# Raspi-TPUART_v1_2.net
KiCad netlist of a schematic drawn in EAGLE
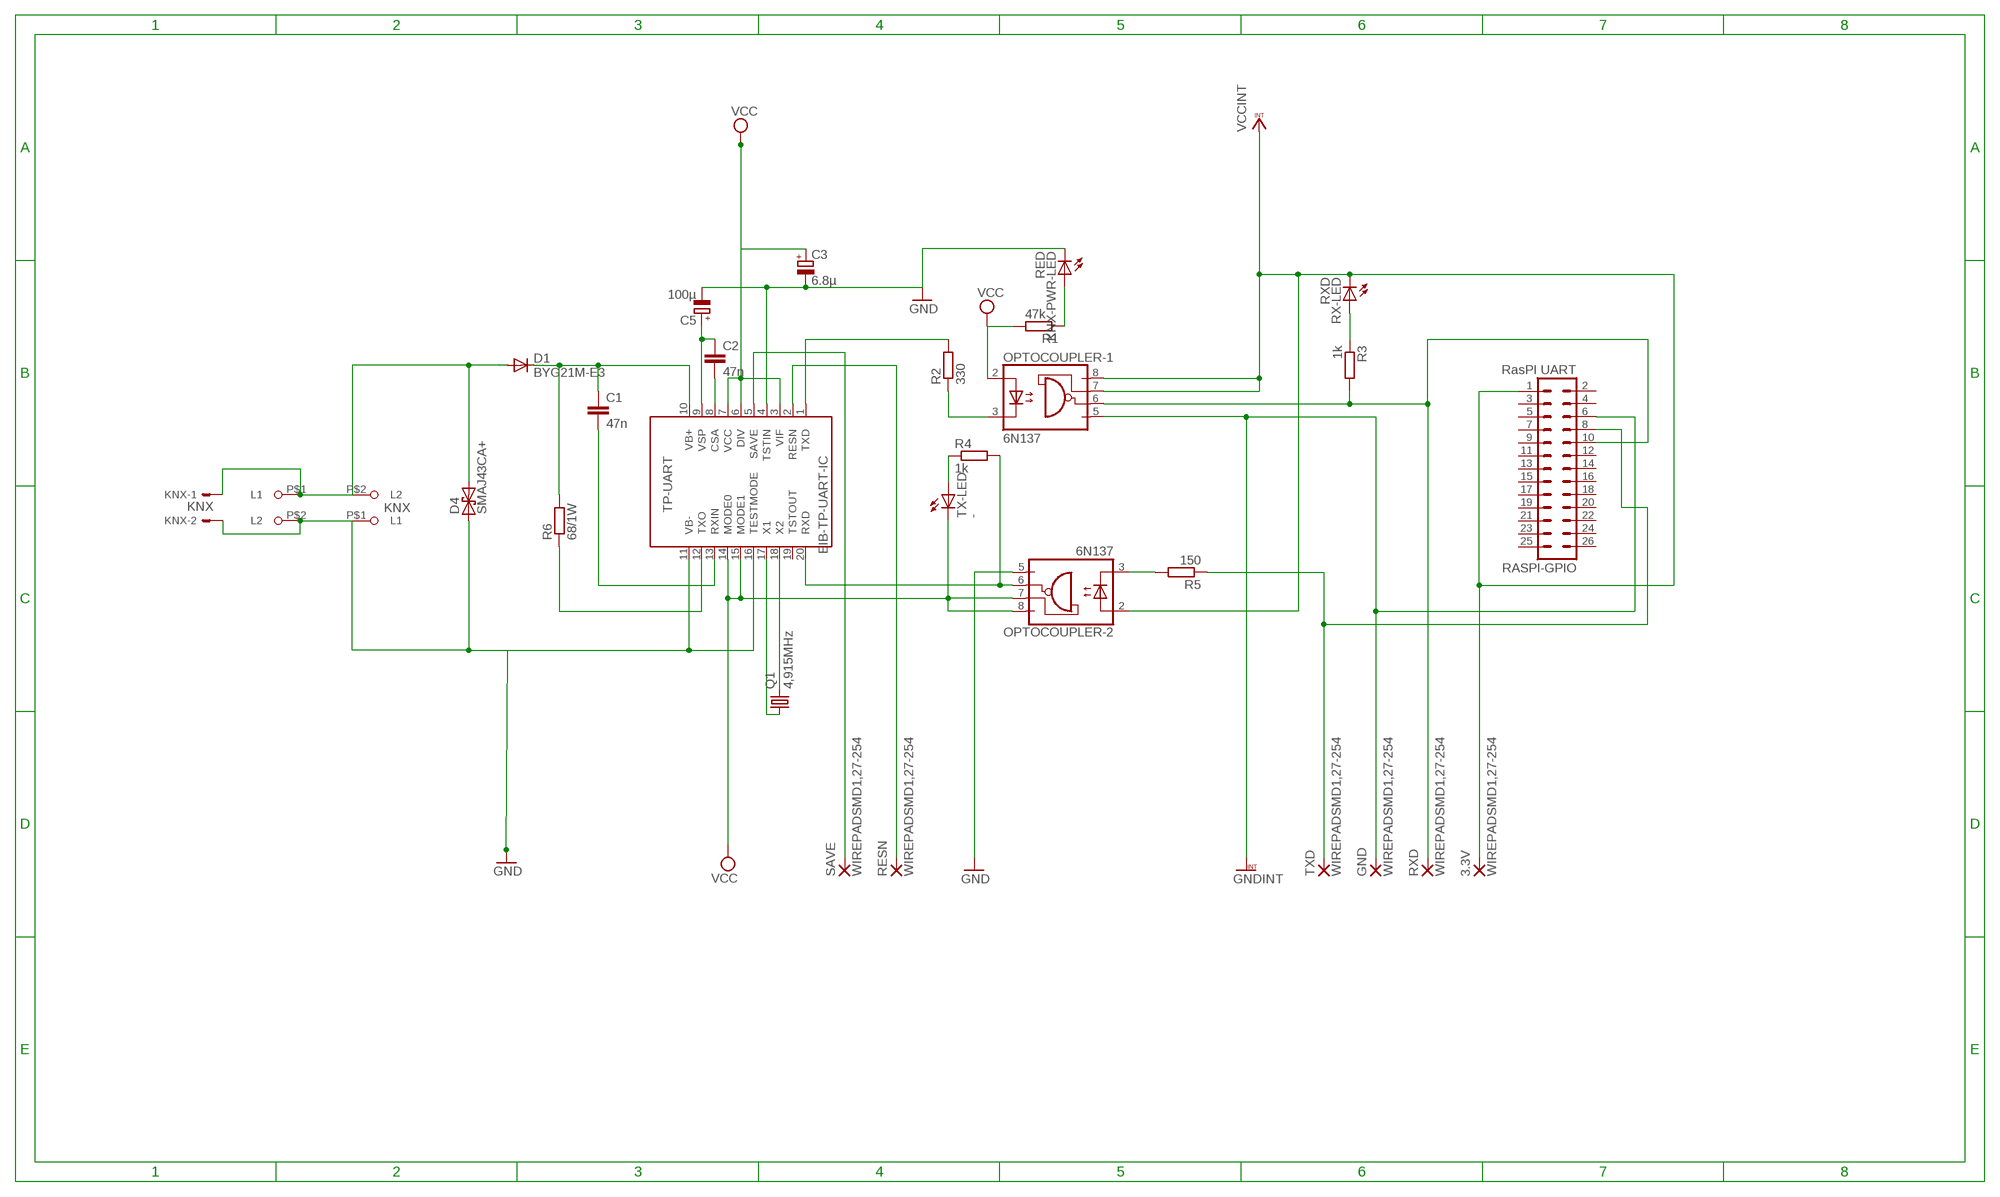
[diagram p0: schematic, sheet 1]

(export (version "E")
  (design (tool "Eeschema 10.0.6"))
  (components
    (comp (ref "3.3V")
      (value "WIREPADSMD1,27-254")
      (footprint "eagle-import:SMD1,27-2,54")
      (libsource (lib "eagle-import") (part "WIREPADSMD1,27-254"))
    )
    (comp (ref "C1")
      (value "47n")
      (footprint "eagle-import:C1206")
      (libsource (lib "eagle-import") (part "C-EUC1206"))
    )
    (comp (ref "C2")
      (value "47n")
      (footprint "eagle-import:C1206")
      (libsource (lib "eagle-import") (part "C-EUC1206"))
    )
    (comp (ref "C3")
      (value "6.8µ")
      (footprint "eagle-import:D_7343-31R")
      (libsource (lib "eagle-import") (part "CPOL-EUD/7343-31R"))
    )
    (comp (ref "C5")
      (value "100µ")
      (footprint "eagle-import:D_7343-31R")
      (libsource (lib "eagle-import") (part "CPOL-EUD/7343-31R"))
    )
    (comp (ref "D1")
      (value "BYG21M-E3")
      (footprint "eagle-import:SMB")
      (libsource (lib "eagle-import") (part "ES2D"))
    )
    (comp (ref "D4")
      (value "SMAJ43CA+")
      (footprint "eagle-import:DO214AA")
      (libsource (lib "eagle-import") (part "BZW04XXB"))
    )
    (comp (ref "EIB-TP-UART-IC")
      (value "TP-UART")
      (footprint "eagle-import:SOIC20")
      (libsource (lib "eagle-import") (part "TP-UART"))
    )
    (comp (ref "GND")
      (value "WIREPADSMD1,27-254")
      (footprint "eagle-import:SMD1,27-2,54")
      (libsource (lib "eagle-import") (part "WIREPADSMD1,27-254"))
    )
    (comp (ref "KNX")
      (value "KNX")
      (footprint "eagle-import:22-23-2021")
      (fields (field (name "MF") "MOLEX") (field (name "MPN") "22-23-2021"))
      (libsource (lib "eagle-import") (part "22-23-2021"))
    )
    (comp (ref "KNX-PWR-LED")
      (value "RED")
      (footprint "eagle-import:KA-3528ASYC")
      (libsource (lib "eagle-import") (part "LEDKA-3528ASYC"))
    )
    (comp (ref "KNX_WAGO_243")
      (value "243-211")
      (footprint "eagle-import:243-211")
      (libsource (lib "eagle-import") (part "243-211"))
    )
    (comp (ref "OPTOCOUPLER-1")
      (value "6N137")
      (footprint "eagle-import:DIL8-SMD")
      (libsource (lib "eagle-import") (part "6N137"))
    )
    (comp (ref "OPTOCOUPLER-2")
      (value "6N137")
      (footprint "eagle-import:DIL8-SMD")
      (libsource (lib "eagle-import") (part "6N137"))
    )
    (comp (ref "Q1")
      (value "4,915MHz")
      (footprint "eagle-import:HC49UP")
      (libsource (lib "eagle-import") (part "CRYSTALHC49UP"))
    )
    (comp (ref "R1")
      (value "47k")
      (footprint "eagle-import:M1206")
      (libsource (lib "eagle-import") (part "R-EU_M1206"))
    )
    (comp (ref "R2")
      (value "330")
      (footprint "eagle-import:M1206")
      (libsource (lib "eagle-import") (part "R-EU_M1206"))
    )
    (comp (ref "R3")
      (value "1k")
      (footprint "eagle-import:M1206")
      (libsource (lib "eagle-import") (part "R-EU_M1206"))
    )
    (comp (ref "R4")
      (value "1k")
      (footprint "eagle-import:M1206")
      (libsource (lib "eagle-import") (part "R-EU_M1206"))
    )
    (comp (ref "R5")
      (value "150")
      (footprint "eagle-import:M1206")
      (libsource (lib "eagle-import") (part "R-EU_M1206"))
    )
    (comp (ref "R6")
      (value "68/1W")
      (footprint "eagle-import:R2512")
      (libsource (lib "eagle-import") (part "R-EU_R2512"))
    )
    (comp (ref "RASPI-GPIO")
      (value "RasPI UART")
      (footprint "eagle-import:MA13-2")
      (libsource (lib "eagle-import") (part "MA13-2"))
    )
    (comp (ref "RESN")
      (value "WIREPADSMD1,27-254")
      (footprint "eagle-import:SMD1,27-2,54")
      (libsource (lib "eagle-import") (part "WIREPADSMD1,27-254"))
    )
    (comp (ref "RX-LED")
      (value "RXD")
      (footprint "eagle-import:KA-3528ASYC")
      (libsource (lib "eagle-import") (part "LEDKA-3528ASYC"))
    )
    (comp (ref "RXD")
      (value "WIREPADSMD1,27-254")
      (footprint "eagle-import:SMD1,27-2,54")
      (libsource (lib "eagle-import") (part "WIREPADSMD1,27-254"))
    )
    (comp (ref "SAVE")
      (value "WIREPADSMD1,27-254")
      (footprint "eagle-import:SMD1,27-2,54")
      (libsource (lib "eagle-import") (part "WIREPADSMD1,27-254"))
    )
    (comp (ref "TX-LED")
      (value "-")
      (footprint "eagle-import:KA-3528ASYC")
      (libsource (lib "eagle-import") (part "LEDKA-3528ASYC"))
    )
    (comp (ref "TXD")
      (value "WIREPADSMD1,27-254")
      (footprint "eagle-import:SMD1,27-2,54")
      (libsource (lib "eagle-import") (part "WIREPADSMD1,27-254"))
    )
    (comp (ref "U$1")
      (value "243-211")
      (footprint "eagle-import:243-211")
      (libsource (lib "eagle-import") (part "243-211"))
    )
  )
  (nets
    (net (code "1") (name "GND") (class "Default")
      (node (ref "C3") (pin "-") (pinfunction "-_-") (pintype "passive"))
      (node (ref "C5") (pin "-") (pinfunction "-_-") (pintype "passive"))
      (node (ref "D4") (pin "A") (pinfunction "1_A") (pintype "passive"))
      (node (ref "EIB-TP-UART-IC") (pin "11") (pinfunction "VB-_11") (pintype "passive"))
      (node (ref "EIB-TP-UART-IC") (pin "16") (pinfunction "TESTMODE_16") (pintype "input"))
      (node (ref "EIB-TP-UART-IC") (pin "4") (pinfunction "TSTIN_4") (pintype "bidirectional"))
      (node (ref "KNX") (pin "2") (pinfunction "S_2") (pintype "passive"))
      (node (ref "KNX-PWR-LED") (pin "C") (pinfunction "C_C") (pintype "passive"))
      (node (ref "KNX_WAGO_243") (pin "P$1") (pinfunction "L1_P$1") (pintype "bidirectional"))
      (node (ref "OPTOCOUPLER-2") (pin "5") (pinfunction "GND_5") (pintype "passive"))
      (node (ref "U$1") (pin "P$2") (pinfunction "L2_P$2") (pintype "bidirectional"))
    )
    (net (code "2") (name "GNDINT") (class "Default")
      (node (ref "GND") (pin "1") (pinfunction "P_1") (pintype "passive"))
      (node (ref "OPTOCOUPLER-1") (pin "5") (pinfunction "GND_5") (pintype "passive"))
      (node (ref "RASPI-GPIO") (pin "6") (pinfunction "6_6") (pintype "passive"))
    )
    (net (code "3") (name "Net-(D4-2)") (class "Default")
      (node (ref "D1") (pin "A") (pinfunction "A_A") (pintype "passive"))
      (node (ref "D4") (pin "C") (pinfunction "2_C") (pintype "passive"))
      (node (ref "KNX") (pin "1") (pinfunction "S_1") (pintype "passive"))
      (node (ref "KNX_WAGO_243") (pin "P$2") (pinfunction "L2_P$2") (pintype "bidirectional"))
      (node (ref "U$1") (pin "P$1") (pinfunction "L1_P$1") (pintype "bidirectional"))
    )
    (net (code "4") (name "Net-(EIB-TP-UART-IC-CSA)") (class "Default")
      (node (ref "C2") (pin "2") (pinfunction "2_2") (pintype "passive"))
      (node (ref "EIB-TP-UART-IC") (pin "8") (pinfunction "CSA_8") (pintype "passive"))
    )
    (net (code "5") (name "Net-(EIB-TP-UART-IC-RESN)") (class "Default")
      (node (ref "EIB-TP-UART-IC") (pin "2") (pinfunction "RESN_2") (pintype "bidirectional"))
      (node (ref "RESN") (pin "1") (pinfunction "P_1") (pintype "passive"))
    )
    (net (code "6") (name "Net-(EIB-TP-UART-IC-RXD)") (class "Default")
      (node (ref "EIB-TP-UART-IC") (pin "20") (pinfunction "RXD_20") (pintype "input"))
      (node (ref "OPTOCOUPLER-2") (pin "6") (pinfunction "VO_6") (pintype "passive"))
      (node (ref "R4") (pin "2") (pinfunction "2_2") (pintype "passive"))
    )
    (net (code "7") (name "Net-(EIB-TP-UART-IC-RXIN)") (class "Default")
      (node (ref "C1") (pin "2") (pinfunction "2_2") (pintype "passive"))
      (node (ref "EIB-TP-UART-IC") (pin "13") (pinfunction "RXIN_13") (pintype "input"))
    )
    (net (code "8") (name "Net-(EIB-TP-UART-IC-SAVE)") (class "Default")
      (node (ref "EIB-TP-UART-IC") (pin "5") (pinfunction "SAVE_5") (pintype "open_collector"))
      (node (ref "SAVE") (pin "1") (pinfunction "P_1") (pintype "passive"))
    )
    (net (code "9") (name "Net-(EIB-TP-UART-IC-TXD)") (class "Default")
      (node (ref "EIB-TP-UART-IC") (pin "1") (pinfunction "TXD_1") (pintype "output"))
      (node (ref "R2") (pin "2") (pinfunction "2_2") (pintype "passive"))
    )
    (net (code "10") (name "Net-(EIB-TP-UART-IC-TXO)") (class "Default")
      (node (ref "EIB-TP-UART-IC") (pin "12") (pinfunction "TXO_12") (pintype "output"))
      (node (ref "R6") (pin "1") (pinfunction "1_1") (pintype "passive"))
    )
    (net (code "11") (name "Net-(EIB-TP-UART-IC-VB+)") (class "Default")
      (node (ref "C1") (pin "1") (pinfunction "1_1") (pintype "passive"))
      (node (ref "D1") (pin "C") (pinfunction "C_C") (pintype "passive"))
      (node (ref "EIB-TP-UART-IC") (pin "10") (pinfunction "VB+_10") (pintype "passive"))
      (node (ref "R6") (pin "2") (pinfunction "2_2") (pintype "passive"))
    )
    (net (code "12") (name "Net-(EIB-TP-UART-IC-VSP)") (class "Default")
      (node (ref "C2") (pin "1") (pinfunction "1_1") (pintype "passive"))
      (node (ref "C5") (pin "+") (pinfunction "+_+") (pintype "passive"))
      (node (ref "EIB-TP-UART-IC") (pin "9") (pinfunction "VSP_9") (pintype "passive"))
    )
    (net (code "13") (name "Net-(EIB-TP-UART-IC-X1)") (class "Default")
      (node (ref "EIB-TP-UART-IC") (pin "17") (pinfunction "X1_17") (pintype "passive"))
      (node (ref "Q1") (pin "1") (pinfunction "1_1") (pintype "passive"))
    )
    (net (code "14") (name "Net-(EIB-TP-UART-IC-X2)") (class "Default")
      (node (ref "EIB-TP-UART-IC") (pin "18") (pinfunction "X2_18") (pintype "passive"))
      (node (ref "Q1") (pin "2") (pinfunction "2_2") (pintype "passive"))
    )
    (net (code "15") (name "Net-(KNX-PWR-LED-PadA)") (class "Default")
      (node (ref "KNX-PWR-LED") (pin "A") (pinfunction "A_A") (pintype "passive"))
      (node (ref "R1") (pin "1") (pinfunction "1_1") (pintype "passive"))
    )
    (net (code "16") (name "Net-(OPTOCOUPLER-1-C)") (class "Default")
      (node (ref "OPTOCOUPLER-1") (pin "3") (pinfunction "C_3") (pintype "passive"))
      (node (ref "R2") (pin "1") (pinfunction "1_1") (pintype "passive"))
    )
    (net (code "17") (name "Net-(OPTOCOUPLER-1-VO)") (class "Default")
      (node (ref "OPTOCOUPLER-1") (pin "6") (pinfunction "VO_6") (pintype "passive"))
      (node (ref "R3") (pin "2") (pinfunction "2_2") (pintype "passive"))
      (node (ref "RASPI-GPIO") (pin "10") (pinfunction "10_10") (pintype "passive"))
      (node (ref "RXD") (pin "1") (pinfunction "P_1") (pintype "passive"))
    )
    (net (code "18") (name "Net-(OPTOCOUPLER-2-C)") (class "Default")
      (node (ref "OPTOCOUPLER-2") (pin "3") (pinfunction "C_3") (pintype "passive"))
      (node (ref "R5") (pin "2") (pinfunction "2_2") (pintype "passive"))
    )
    (net (code "19") (name "Net-(R3-Pad1)") (class "Default")
      (node (ref "R3") (pin "1") (pinfunction "1_1") (pintype "passive"))
      (node (ref "RX-LED") (pin "A") (pinfunction "A_A") (pintype "passive"))
    )
    (net (code "20") (name "Net-(R4-Pad1)") (class "Default")
      (node (ref "R4") (pin "1") (pinfunction "1_1") (pintype "passive"))
      (node (ref "TX-LED") (pin "A") (pinfunction "A_A") (pintype "passive"))
    )
    (net (code "21") (name "Net-(TXD-P)") (class "Default")
      (node (ref "R5") (pin "1") (pinfunction "1_1") (pintype "passive"))
      (node (ref "RASPI-GPIO") (pin "8") (pinfunction "8_8") (pintype "passive"))
      (node (ref "TXD") (pin "1") (pinfunction "P_1") (pintype "passive"))
    )
    (net (code "22") (name "VCC") (class "Default")
      (node (ref "C3") (pin "+") (pinfunction "+_+") (pintype "passive"))
      (node (ref "EIB-TP-UART-IC") (pin "14") (pinfunction "MODE0_14") (pintype "input"))
      (node (ref "EIB-TP-UART-IC") (pin "15") (pinfunction "MODE1_15") (pintype "input"))
      (node (ref "EIB-TP-UART-IC") (pin "3") (pinfunction "VIF_3") (pintype "input"))
      (node (ref "EIB-TP-UART-IC") (pin "6") (pinfunction "DIV_6") (pintype "input"))
      (node (ref "EIB-TP-UART-IC") (pin "7") (pinfunction "VCC_7") (pintype "output"))
      (node (ref "OPTOCOUPLER-1") (pin "2") (pinfunction "A_2") (pintype "passive"))
      (node (ref "OPTOCOUPLER-2") (pin "7") (pinfunction "VE_7") (pintype "passive"))
      (node (ref "OPTOCOUPLER-2") (pin "8") (pinfunction "VCC_8") (pintype "passive"))
      (node (ref "R1") (pin "2") (pinfunction "2_2") (pintype "passive"))
      (node (ref "TX-LED") (pin "C") (pinfunction "C_C") (pintype "passive"))
    )
    (net (code "23") (name "VCCINT") (class "Default")
      (node (ref "3.3V") (pin "1") (pinfunction "P_1") (pintype "passive"))
      (node (ref "OPTOCOUPLER-1") (pin "7") (pinfunction "VE_7") (pintype "passive"))
      (node (ref "OPTOCOUPLER-1") (pin "8") (pinfunction "VCC_8") (pintype "passive"))
      (node (ref "OPTOCOUPLER-2") (pin "2") (pinfunction "A_2") (pintype "passive"))
      (node (ref "RASPI-GPIO") (pin "1") (pinfunction "1_1") (pintype "passive"))
      (node (ref "RX-LED") (pin "C") (pinfunction "C_C") (pintype "passive"))
    )
    (net (code "24") (name "unconnected-(EIB-TP-UART-IC-TSTOUT-Pad19)") (class "Default")
      (node (ref "EIB-TP-UART-IC") (pin "19") (pinfunction "TSTOUT_19") (pintype "output"))
    )
    (net (code "25") (name "unconnected-(RASPI-GPIO-Pad2)") (class "Default")
      (node (ref "RASPI-GPIO") (pin "2") (pinfunction "2_2") (pintype "passive"))
    )
    (net (code "26") (name "unconnected-(RASPI-GPIO-Pad3)") (class "Default")
      (node (ref "RASPI-GPIO") (pin "3") (pinfunction "3_3") (pintype "passive"))
    )
    (net (code "27") (name "unconnected-(RASPI-GPIO-Pad4)") (class "Default")
      (node (ref "RASPI-GPIO") (pin "4") (pinfunction "4_4") (pintype "passive"))
    )
    (net (code "28") (name "unconnected-(RASPI-GPIO-Pad5)") (class "Default")
      (node (ref "RASPI-GPIO") (pin "5") (pinfunction "5_5") (pintype "passive"))
    )
    (net (code "29") (name "unconnected-(RASPI-GPIO-Pad7)") (class "Default")
      (node (ref "RASPI-GPIO") (pin "7") (pinfunction "7_7") (pintype "passive"))
    )
    (net (code "30") (name "unconnected-(RASPI-GPIO-Pad9)") (class "Default")
      (node (ref "RASPI-GPIO") (pin "9") (pinfunction "9_9") (pintype "passive"))
    )
    (net (code "31") (name "unconnected-(RASPI-GPIO-Pad11)") (class "Default")
      (node (ref "RASPI-GPIO") (pin "11") (pinfunction "11_11") (pintype "passive"))
    )
    (net (code "32") (name "unconnected-(RASPI-GPIO-Pad12)") (class "Default")
      (node (ref "RASPI-GPIO") (pin "12") (pinfunction "12_12") (pintype "passive"))
    )
    (net (code "33") (name "unconnected-(RASPI-GPIO-Pad13)") (class "Default")
      (node (ref "RASPI-GPIO") (pin "13") (pinfunction "13_13") (pintype "passive"))
    )
    (net (code "34") (name "unconnected-(RASPI-GPIO-Pad14)") (class "Default")
      (node (ref "RASPI-GPIO") (pin "14") (pinfunction "14_14") (pintype "passive"))
    )
    (net (code "35") (name "unconnected-(RASPI-GPIO-Pad15)") (class "Default")
      (node (ref "RASPI-GPIO") (pin "15") (pinfunction "15_15") (pintype "passive"))
    )
    (net (code "36") (name "unconnected-(RASPI-GPIO-Pad16)") (class "Default")
      (node (ref "RASPI-GPIO") (pin "16") (pinfunction "16_16") (pintype "passive"))
    )
    (net (code "37") (name "unconnected-(RASPI-GPIO-Pad17)") (class "Default")
      (node (ref "RASPI-GPIO") (pin "17") (pinfunction "17_17") (pintype "passive"))
    )
    (net (code "38") (name "unconnected-(RASPI-GPIO-Pad18)") (class "Default")
      (node (ref "RASPI-GPIO") (pin "18") (pinfunction "18_18") (pintype "passive"))
    )
    (net (code "39") (name "unconnected-(RASPI-GPIO-Pad19)") (class "Default")
      (node (ref "RASPI-GPIO") (pin "19") (pinfunction "19_19") (pintype "passive"))
    )
    (net (code "40") (name "unconnected-(RASPI-GPIO-Pad20)") (class "Default")
      (node (ref "RASPI-GPIO") (pin "20") (pinfunction "20_20") (pintype "passive"))
    )
    (net (code "41") (name "unconnected-(RASPI-GPIO-Pad21)") (class "Default")
      (node (ref "RASPI-GPIO") (pin "21") (pinfunction "21_21") (pintype "passive"))
    )
    (net (code "42") (name "unconnected-(RASPI-GPIO-Pad22)") (class "Default")
      (node (ref "RASPI-GPIO") (pin "22") (pinfunction "22_22") (pintype "passive"))
    )
    (net (code "43") (name "unconnected-(RASPI-GPIO-Pad23)") (class "Default")
      (node (ref "RASPI-GPIO") (pin "23") (pinfunction "23_23") (pintype "passive"))
    )
    (net (code "44") (name "unconnected-(RASPI-GPIO-Pad24)") (class "Default")
      (node (ref "RASPI-GPIO") (pin "24") (pinfunction "24_24") (pintype "passive"))
    )
    (net (code "45") (name "unconnected-(RASPI-GPIO-Pad25)") (class "Default")
      (node (ref "RASPI-GPIO") (pin "25") (pinfunction "25_25") (pintype "passive"))
    )
    (net (code "46") (name "unconnected-(RASPI-GPIO-Pad26)") (class "Default")
      (node (ref "RASPI-GPIO") (pin "26") (pinfunction "26_26") (pintype "passive"))
    )
  )
)
